# External_Connectors.net
KiCad netlist of a schematic drawn in Altium Designer
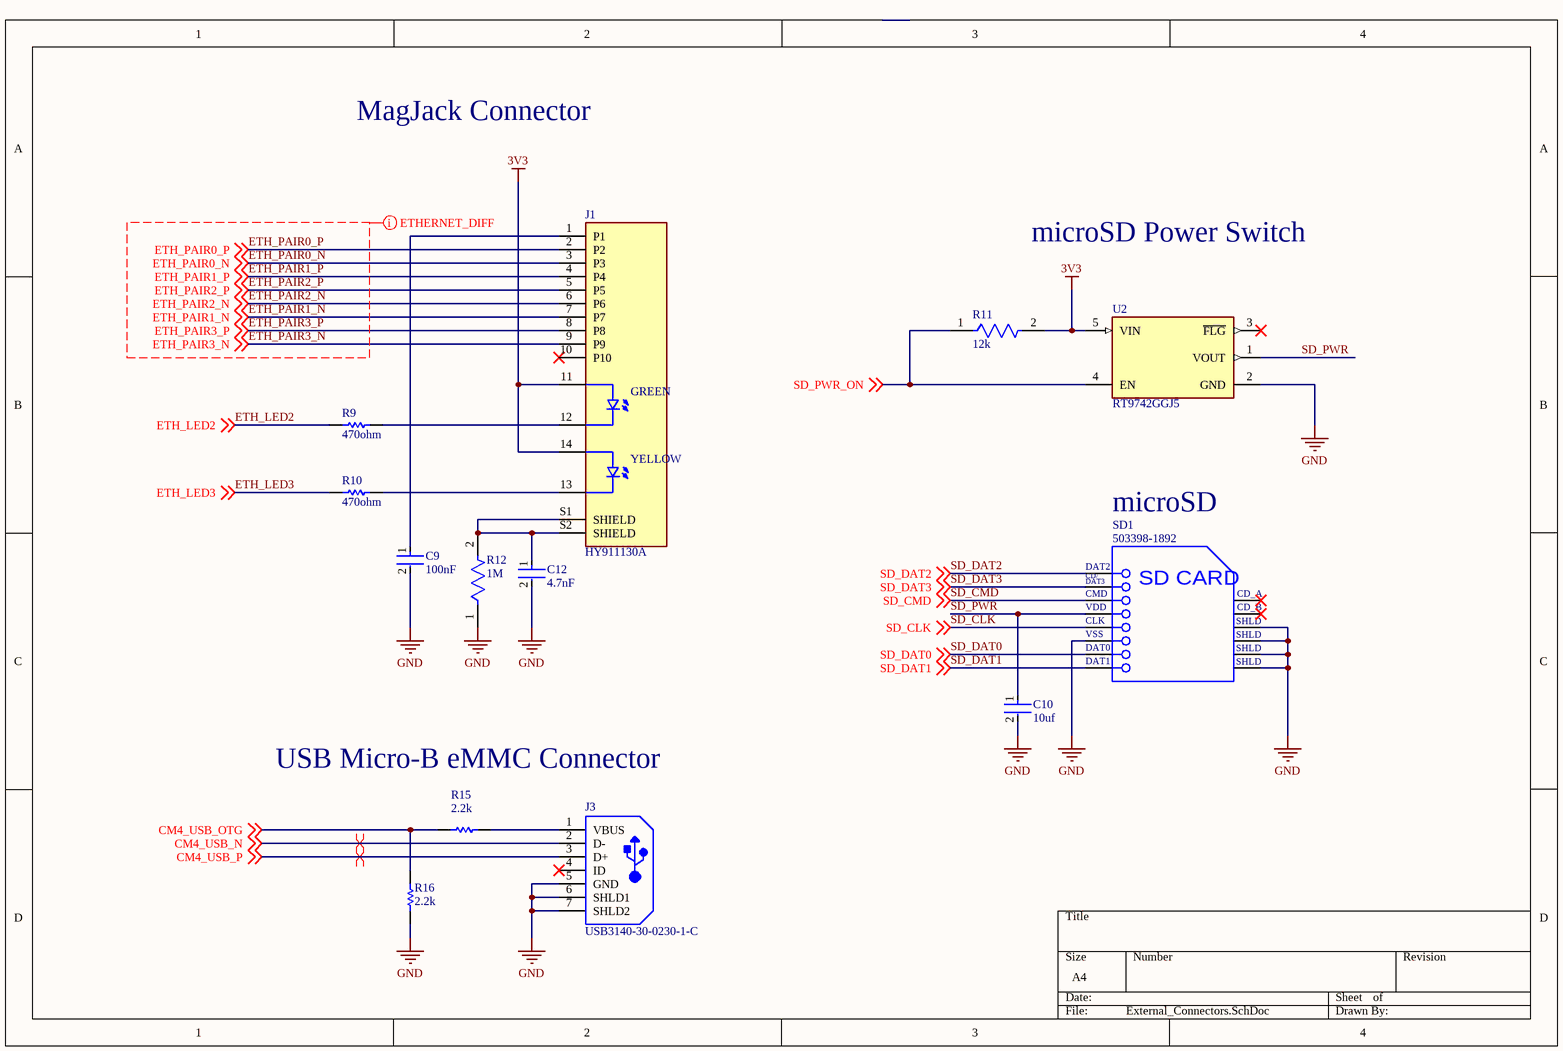
[diagram p0: External_Connectors.SchDoc]

(export (version "E")
  (design (tool "Eeschema 10.0.6"))
  (components
    (comp (ref "C9")
      (value "100nF")
      (footprint "FP-C0402-BB-MFG")
      (description "CAP CER 0.1UF 10V X5R 0402")
      (fields (field (name "MANUFACTURER") "Kemet") (field (name "TOLERANCE") "0.1"))
      (libsource (lib "Altium Content Vault") (part "b4654b650e69147ec39a6b967a45e02"))
    )
    (comp (ref "C10")
      (value "10uf")
      (footprint "FP-GRM188-0_2-IPC_C")
      (description "Chip Multilayer Ceramic Capacitors for General Purpose, 0603, 10uF, X5R, 15%, 20%, 35V")
      (fields (field (name "TOLERANCE") "20%"))
      (libsource (lib "Altium Content Vault") (part "11868f565c42a9108669ba33697ecf6"))
    )
    (comp (ref "C12")
      (value "4.7nF")
      (footprint "FP-0805-L_2_01_0_2-W_1_25-IPC_B")
      (description "General Purpose Ceramic Capacitor, 0805, 4.7nF, 10%, X7R, 0.15, 50V")
      (fields (field (name "VOLTAGE") "50V") (field (name "TOLERANCE") "10%"))
      (libsource (lib "Altium Content Vault") (part "02cd4be3c70576c341d710602a673aa"))
    )
    (comp (ref "J1")
      (value "HY911130A")
      (footprint "HANRUN_HR911130A")
      (fields (field (name "MF") "hanrun"))
      (libsource (lib "HR911130A") (part "HR911130A"))
    )
    (comp (ref "J3")
      (value "USB3140-30-0230-1-C")
      (footprint "GCT-USB3140_V")
      (fields
        (field (name "PARTNUMBER") "USB3140")
        (field (name "MANUFACTURER") "Global Connector Technology")
      )
      (libsource (lib "Altium Content Vault") (part "USB-5-2SHLD"))
    )
    (comp (ref "R9")
      (value "470ohm")
      (footprint "RESC1005X40X25ML05T10")
      (fields (field (name "PART NUMBER") "RC0402FR-07470RL") (field (name "MANUFACTURER") "Yageo / Phycomp"))
      (libsource (lib "Altium Content Vault") (part "RES"))
    )
    (comp (ref "R10")
      (value "470ohm")
      (footprint "RESC1005X40X25ML05T10")
      (fields (field (name "PART NUMBER") "RC0402FR-07470RL") (field (name "MANUFACTURER") "Yageo / Phycomp"))
      (libsource (lib "Altium Content Vault") (part "RES"))
    )
    (comp (ref "R11")
      (value "12k")
      (footprint "FP-RC0402-0_4-IPC_C")
      (description "RES SMD 12K OHM 1% 1/16W 0402")
      (fields (field (name "TOLERANCE") "1%"))
      (libsource (lib "Altium Content Vault") (part "1029c3af85768c4190bb7ad29bc67b5"))
    )
    (comp (ref "R12")
      (value "1M")
      (footprint "FP-ERJ6EN-IPC_A")
      (description "RES SMD 1M OHM 1% 1/8W 0805")
      (fields (field (name "TOLERANCE") "1%"))
      (libsource (lib "Altium Content Vault") (part "1029c3af85768c4190bb7ad29bc67b5"))
    )
    (comp (ref "R15")
      (value "2.2k")
      (footprint "RESC1005X40X25LL05T05")
      (fields (field (name "MANUFACTURER") "Panasonic"))
      (libsource (lib "Altium Content Vault") (part "RES-2"))
    )
    (comp (ref "R16")
      (value "2.2k")
      (footprint "RESC1005X40X25LL05T05")
      (fields (field (name "MANUFACTURER") "Panasonic"))
      (libsource (lib "Altium Content Vault") (part "RES-2"))
    )
    (comp (ref "SD1")
      (value "503398-1892")
      (footprint "MOLX-503398-1892_V")
      (description "Micro SD Connector, Pitch 1.1 mm, 8 Position, Height 1.4 mm, -25 to 85 degC, RoHS, Tape and Reel")
      (fields (field (name "MANUFACTURER") "Molex"))
      (libsource (lib "Altium Content Vault") (part "CN-SD-8-2SW-4S"))
    )
    (comp (ref "U2")
      (value "RT9742GGJ5")
      (footprint "FP-RT9742GGJ5-IPC_C")
      (description "IC PWR SWTCH N-CHAN 1:1 TSOT23-5")
      (libsource (lib "Altium Content Vault") (part "6b3db7b45087fee8fb60b49bef92a32"))
    )
  )
  (nets
    (net (code "1") (name "/SD_PWR") (class "Default")
      (node (ref "C10") (pin "1") (pinfunction "1_1") (pintype "passive"))
      (node (ref "SD1") (pin "4") (pinfunction "VDD_4") (pintype "passive"))
      (node (ref "U2") (pin "1") (pinfunction "VOUT_1") (pintype "output"))
    )
    (net (code "2") (name "3V3") (class "Default")
      (node (ref "J1") (pin "11") (pinfunction "11_11") (pintype "passive"))
      (node (ref "J1") (pin "14") (pinfunction "14_14") (pintype "passive"))
      (node (ref "R11") (pin "2") (pinfunction "2_2") (pintype "passive"))
      (node (ref "U2") (pin "5") (pinfunction "VIN_5") (pintype "input"))
    )
    (net (code "3") (name "CM4_USB_N") (class "Default")
      (node (ref "J3") (pin "2") (pinfunction "D-_2") (pintype "passive"))
    )
    (net (code "4") (name "CM4_USB_OTG") (class "Default")
      (node (ref "R15") (pin "1") (pinfunction "1_1") (pintype "passive"))
      (node (ref "R16") (pin "2") (pinfunction "2_2") (pintype "passive"))
    )
    (net (code "5") (name "CM4_USB_P") (class "Default")
      (node (ref "J3") (pin "3") (pinfunction "D+_3") (pintype "passive"))
    )
    (net (code "6") (name "ETH_LED2") (class "Default")
      (node (ref "R9") (pin "1") (pinfunction "1_1") (pintype "passive"))
    )
    (net (code "7") (name "ETH_LED3") (class "Default")
      (node (ref "R10") (pin "1") (pinfunction "1_1") (pintype "passive"))
    )
    (net (code "8") (name "ETH_PAIR0_N") (class "Default")
      (node (ref "J1") (pin "3") (pinfunction "P3_3") (pintype "passive"))
    )
    (net (code "9") (name "ETH_PAIR0_P") (class "Default")
      (node (ref "J1") (pin "2") (pinfunction "P2_2") (pintype "passive"))
    )
    (net (code "10") (name "ETH_PAIR1_N") (class "Default")
      (node (ref "J1") (pin "7") (pinfunction "P7_7") (pintype "passive"))
    )
    (net (code "11") (name "ETH_PAIR1_P") (class "Default")
      (node (ref "J1") (pin "4") (pinfunction "P4_4") (pintype "passive"))
    )
    (net (code "12") (name "ETH_PAIR2_N") (class "Default")
      (node (ref "J1") (pin "6") (pinfunction "P6_6") (pintype "passive"))
    )
    (net (code "13") (name "ETH_PAIR2_P") (class "Default")
      (node (ref "J1") (pin "5") (pinfunction "P5_5") (pintype "passive"))
    )
    (net (code "14") (name "ETH_PAIR3_N") (class "Default")
      (node (ref "J1") (pin "9") (pinfunction "P9_9") (pintype "passive"))
    )
    (net (code "15") (name "ETH_PAIR3_P") (class "Default")
      (node (ref "J1") (pin "8") (pinfunction "P8_8") (pintype "passive"))
    )
    (net (code "16") (name "GND") (class "Default")
      (node (ref "C10") (pin "2") (pinfunction "2_2") (pintype "passive"))
      (node (ref "C12") (pin "2") (pinfunction "2_2") (pintype "passive"))
      (node (ref "C9") (pin "2") (pinfunction "2_2") (pintype "passive"))
      (node (ref "J3") (pin "5") (pinfunction "GND_5") (pintype "passive"))
      (node (ref "J3") (pin "6") (pinfunction "SHLD1_6") (pintype "passive"))
      (node (ref "J3") (pin "7") (pinfunction "SHLD2_7") (pintype "passive"))
      (node (ref "R12") (pin "1") (pinfunction "1_1") (pintype "passive"))
      (node (ref "R16") (pin "1") (pinfunction "1_1") (pintype "passive"))
      (node (ref "SD1") (pin "11") (pinfunction "SHLD_11") (pintype "passive"))
      (node (ref "SD1") (pin "12") (pinfunction "SHLD_12") (pintype "passive"))
      (node (ref "SD1") (pin "13") (pinfunction "SHLD_13") (pintype "passive"))
      (node (ref "SD1") (pin "14") (pinfunction "SHLD_14") (pintype "passive"))
      (node (ref "SD1") (pin "6") (pinfunction "VSS_6") (pintype "passive"))
      (node (ref "U2") (pin "2") (pinfunction "GND_2") (pintype "power_in"))
    )
    (net (code "17") (name "Net-(C12-Pad1)") (class "Default")
      (node (ref "C12") (pin "1") (pinfunction "1_1") (pintype "passive"))
      (node (ref "J1") (pin "S1") (pinfunction "SHIELD_S1") (pintype "passive"))
      (node (ref "J1") (pin "S2") (pinfunction "SHIELD_S2") (pintype "passive"))
      (node (ref "R12") (pin "2") (pinfunction "2_2") (pintype "passive"))
    )
    (net (code "18") (name "Net-(J1-P1)") (class "Default")
      (node (ref "C9") (pin "1") (pinfunction "1_1") (pintype "passive"))
      (node (ref "J1") (pin "1") (pinfunction "P1_1") (pintype "passive"))
    )
    (net (code "19") (name "Net-(J1-Pad12)") (class "Default")
      (node (ref "J1") (pin "12") (pinfunction "12_12") (pintype "passive"))
      (node (ref "R9") (pin "2") (pinfunction "2_2") (pintype "passive"))
    )
    (net (code "20") (name "Net-(J1-Pad13)") (class "Default")
      (node (ref "J1") (pin "13") (pinfunction "13_13") (pintype "passive"))
      (node (ref "R10") (pin "2") (pinfunction "2_2") (pintype "passive"))
    )
    (net (code "21") (name "Net-(J3-VBUS)") (class "Default")
      (node (ref "J3") (pin "1") (pinfunction "VBUS_1") (pintype "passive"))
      (node (ref "R15") (pin "2") (pinfunction "2_2") (pintype "passive"))
    )
    (net (code "22") (name "SD_CLK") (class "Default")
      (node (ref "SD1") (pin "5") (pinfunction "CLK_5") (pintype "passive"))
    )
    (net (code "23") (name "SD_CMD") (class "Default")
      (node (ref "SD1") (pin "3") (pinfunction "CMD_3") (pintype "passive"))
    )
    (net (code "24") (name "SD_DAT0") (class "Default")
      (node (ref "SD1") (pin "7") (pinfunction "DAT0_7") (pintype "passive"))
    )
    (net (code "25") (name "SD_DAT1") (class "Default")
      (node (ref "SD1") (pin "8") (pinfunction "DAT1_8") (pintype "passive"))
    )
    (net (code "26") (name "SD_DAT2") (class "Default")
      (node (ref "SD1") (pin "1") (pinfunction "DAT2_1") (pintype "passive"))
    )
    (net (code "27") (name "SD_DAT3") (class "Default")
      (node (ref "SD1") (pin "2") (pinfunction "CD/DAT3_2") (pintype "passive"))
    )
    (net (code "28") (name "SD_PWR_ON") (class "Default")
      (node (ref "R11") (pin "1") (pinfunction "1_1") (pintype "passive"))
      (node (ref "U2") (pin "4") (pinfunction "EN_4") (pintype "passive"))
    )
    (net (code "29") (name "unconnected-(J1-P10-Pad10)") (class "Default")
      (node (ref "J1") (pin "10") (pinfunction "P10_10") (pintype "passive+no_connect"))
    )
    (net (code "30") (name "unconnected-(J3-ID-Pad4)") (class "Default")
      (node (ref "J3") (pin "4") (pinfunction "ID_4") (pintype "passive+no_connect"))
    )
    (net (code "31") (name "unconnected-(SD1-CD_A-Pad9)") (class "Default")
      (node (ref "SD1") (pin "9") (pinfunction "CD_A_9") (pintype "passive+no_connect"))
    )
    (net (code "32") (name "unconnected-(SD1-CD_B-Pad10)") (class "Default")
      (node (ref "SD1") (pin "10") (pinfunction "CD_B_10") (pintype "passive+no_connect"))
    )
    (net (code "33") (name "unconnected-(U2-~{FLG}-Pad3)") (class "Default")
      (node (ref "U2") (pin "3") (pinfunction "~{FLG}_3") (pintype "output+no_connect"))
    )
  )
)
